# Transponder_Proaut_V5.net
KiCad netlist of a schematic drawn in EAGLE
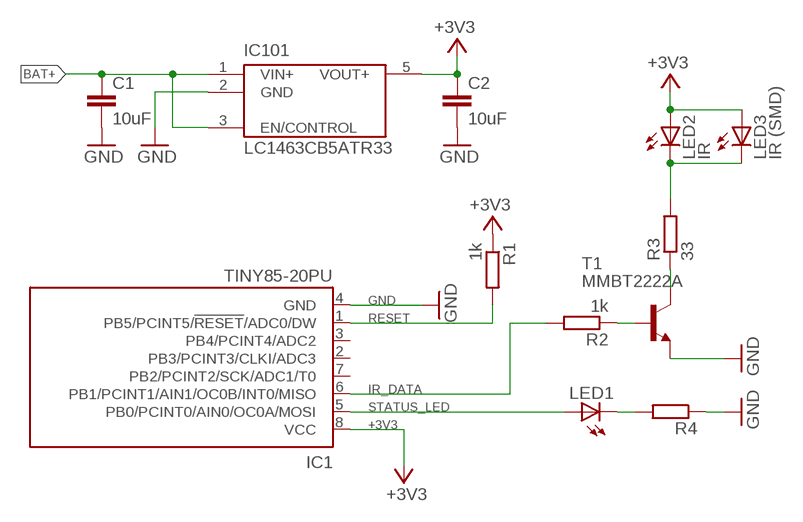
[diagram p0: schematic, sheet 1]

(export (version "E")
  (design (tool "Eeschema 10.0.6"))
  (components
    (comp (ref "C1")
      (value "10uF")
      (footprint "eagle-import:C0805K")
      (libsource (lib "eagle-import") (part "C-EUC0805K"))
    )
    (comp (ref "C2")
      (value "10uF")
      (footprint "eagle-import:C0805K")
      (libsource (lib "eagle-import") (part "C-EUC0805K"))
    )
    (comp (ref "IC1")
      (value "TINY85-20PU")
      (footprint "eagle-import:8S2")
      (fields (field (name "MPN") "ATTINY13-20SU"))
      (libsource (lib "eagle-import") (part "TINY13SU-20"))
    )
    (comp (ref "IC101")
      (value "LC1463CB5ATR33")
      (footprint "eagle-import:SOT23-5")
      (libsource (lib "eagle-import") (part "LP3990"))
    )
    (comp (ref "LED1")
      (value "LEDCHIPLED_0805")
      (footprint "eagle-import:CHIPLED_0805")
      (libsource (lib "eagle-import") (part "LEDCHIPLED_0805"))
    )
    (comp (ref "LED2")
      (value "IR")
      (footprint "eagle-import:LED5MM")
      (libsource (lib "eagle-import") (part "LED5MM"))
    )
    (comp (ref "LED3")
      (value "IR (SMD)")
      (footprint "eagle-import:CHIPLED_0805")
      (libsource (lib "eagle-import") (part "LEDCHIPLED_0805"))
    )
    (comp (ref "R1")
      (value "1k")
      (footprint "eagle-import:R0805@1")
      (libsource (lib "eagle-import") (part "R-EU_R0805"))
    )
    (comp (ref "R2")
      (value "1k")
      (footprint "eagle-import:R0805@1")
      (libsource (lib "eagle-import") (part "R-EU_R0805"))
    )
    (comp (ref "R3")
      (value "33")
      (footprint "eagle-import:R0805@1")
      (libsource (lib "eagle-import") (part "R-EU_R0805"))
    )
    (comp (ref "R4")
      (value "R-EU_R0805")
      (footprint "eagle-import:R0805@1")
      (libsource (lib "eagle-import") (part "R-EU_R0805"))
    )
    (comp (ref "T1")
      (value "MMBT2222A")
      (footprint "eagle-import:SOT23-BEC")
      (libsource (lib "eagle-import") (part "-NPN-SOT23-BECMMBT2222ALT1"))
    )
  )
  (nets
    (net (code "1") (name "+3V3") (class "Default")
      (node (ref "C2") (pin "1") (pinfunction "1_1") (pintype "passive"))
      (node (ref "IC1") (pin "8") (pinfunction "VCC_8") (pintype "power_in"))
      (node (ref "IC101") (pin "5") (pinfunction "VOUT+_5") (pintype "bidirectional"))
      (node (ref "LED2") (pin "A") (pinfunction "A_A") (pintype "passive"))
      (node (ref "LED3") (pin "A") (pinfunction "A_A") (pintype "passive"))
      (node (ref "R1") (pin "1") (pinfunction "1_1") (pintype "passive"))
    )
    (net (code "2") (name "/IR_DATA") (class "Default")
      (node (ref "IC1") (pin "6") (pinfunction "PB1/PCINT1/AIN1/OC0B/INT0/MISO_6") (pintype "bidirectional"))
      (node (ref "R2") (pin "2") (pinfunction "2_2") (pintype "passive"))
    )
    (net (code "3") (name "/RESET") (class "Default")
      (node (ref "IC1") (pin "1") (pinfunction "PB5/PCINT5/~{RESET}/ADC0/DW_1") (pintype "bidirectional"))
      (node (ref "R1") (pin "2") (pinfunction "2_2") (pintype "passive"))
    )
    (net (code "4") (name "/STATUS_LED") (class "Default")
      (node (ref "IC1") (pin "5") (pinfunction "PB0/PCINT0/AIN0/OC0A/MOSI_5") (pintype "bidirectional"))
      (node (ref "LED1") (pin "A") (pinfunction "A_A") (pintype "passive"))
    )
    (net (code "5") (name "BAT+") (class "Default")
      (node (ref "C1") (pin "1") (pinfunction "1_1") (pintype "passive"))
      (node (ref "IC101") (pin "1") (pinfunction "VIN+_1") (pintype "bidirectional"))
      (node (ref "IC101") (pin "3") (pinfunction "EN/CONTROL_3") (pintype "bidirectional"))
    )
    (net (code "6") (name "GND") (class "Default")
      (node (ref "C1") (pin "2") (pinfunction "2_2") (pintype "passive"))
      (node (ref "C2") (pin "2") (pinfunction "2_2") (pintype "passive"))
      (node (ref "IC1") (pin "4") (pinfunction "GND_4") (pintype "power_in"))
      (node (ref "IC101") (pin "2") (pinfunction "GND_2") (pintype "bidirectional"))
      (node (ref "R4") (pin "1") (pinfunction "1_1") (pintype "passive"))
      (node (ref "T1") (pin "E") (pinfunction "E_E") (pintype "passive"))
    )
    (net (code "7") (name "Net-(LED1-PadC)") (class "Default")
      (node (ref "LED1") (pin "C") (pinfunction "C_C") (pintype "passive"))
      (node (ref "R4") (pin "2") (pinfunction "2_2") (pintype "passive"))
    )
    (net (code "8") (name "Net-(LED2-C)") (class "Default")
      (node (ref "LED2") (pin "K") (pinfunction "C_K") (pintype "passive"))
      (node (ref "LED3") (pin "C") (pinfunction "C_C") (pintype "passive"))
      (node (ref "R3") (pin "2") (pinfunction "2_2") (pintype "passive"))
    )
    (net (code "9") (name "Net-(R2-Pad1)") (class "Default")
      (node (ref "R2") (pin "1") (pinfunction "1_1") (pintype "passive"))
      (node (ref "T1") (pin "B") (pinfunction "B_B") (pintype "passive"))
    )
    (net (code "10") (name "Net-(R3-Pad1)") (class "Default")
      (node (ref "R3") (pin "1") (pinfunction "1_1") (pintype "passive"))
      (node (ref "T1") (pin "C") (pinfunction "C_C") (pintype "passive"))
    )
    (net (code "11") (name "unconnected-(IC1-PB2{slash}PCINT2{slash}SCK{slash}ADC1{slash}T0-Pad7)") (class "Default")
      (node (ref "IC1") (pin "7") (pinfunction "PB2/PCINT2/SCK/ADC1/T0_7") (pintype "bidirectional"))
    )
    (net (code "12") (name "unconnected-(IC1-PB3{slash}PCINT3{slash}CLKI{slash}ADC3-Pad2)") (class "Default")
      (node (ref "IC1") (pin "2") (pinfunction "PB3/PCINT3/CLKI/ADC3_2") (pintype "bidirectional"))
    )
    (net (code "13") (name "unconnected-(IC1-PB4{slash}PCINT4{slash}ADC2-Pad3)") (class "Default")
      (node (ref "IC1") (pin "3") (pinfunction "PB4/PCINT4/ADC2_3") (pintype "bidirectional"))
    )
  )
)
